# BSK4.net
KiCad netlist of a schematic drawn in EAGLE
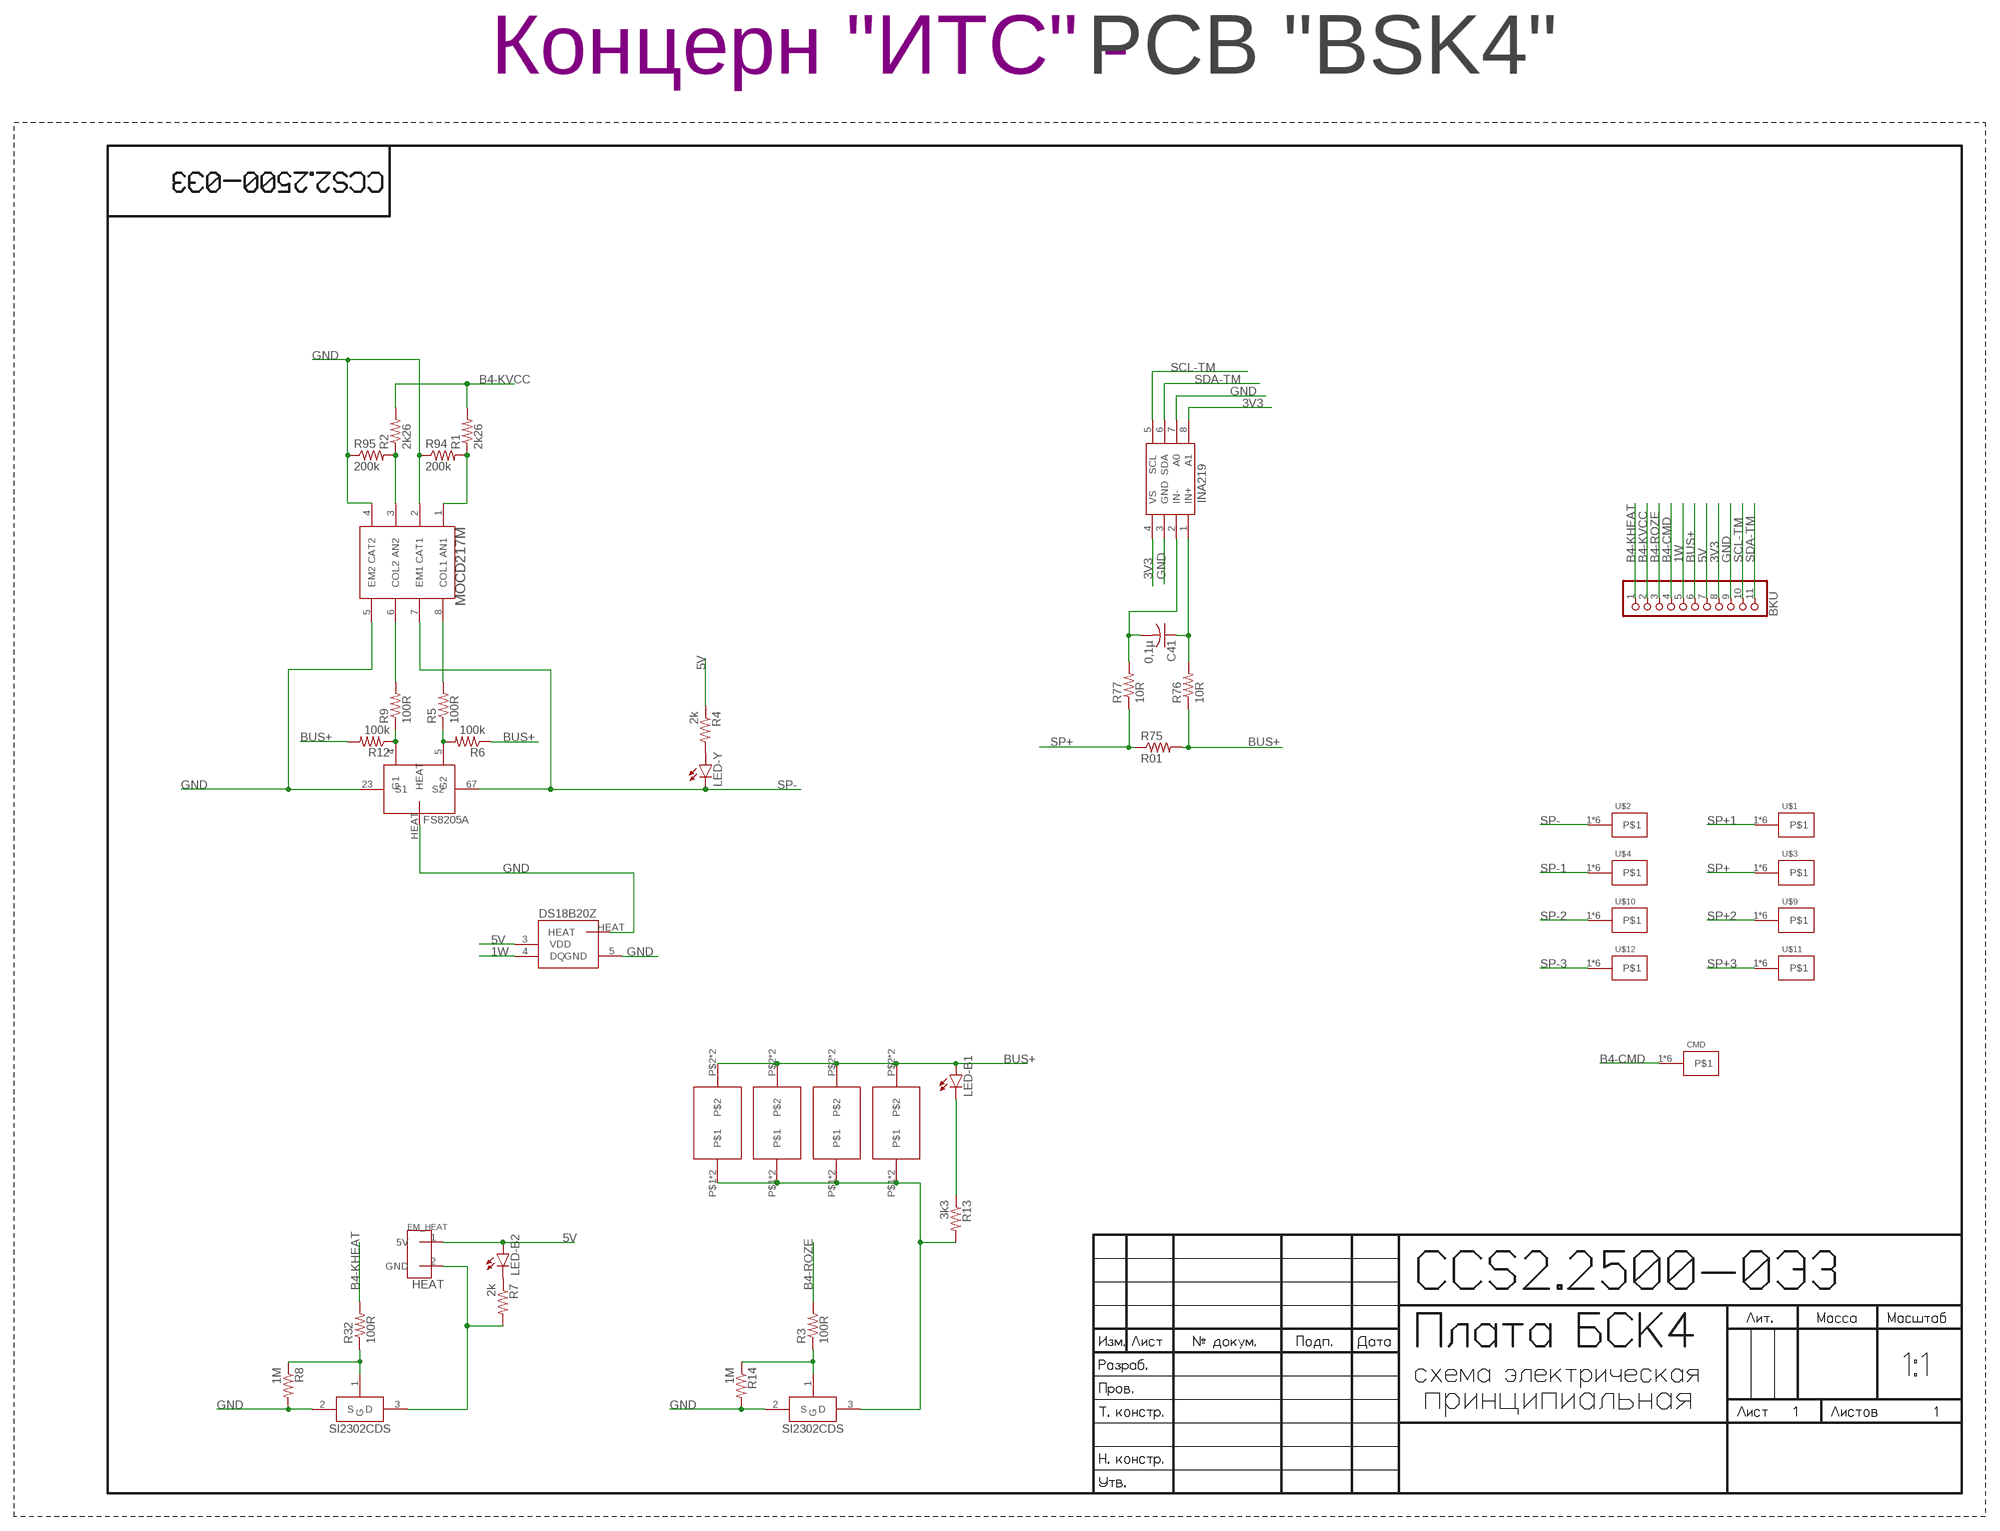
[diagram p0: schematic, sheet 1]

(export (version "E")
  (design (tool "Eeschema 10.0.6"))
  (components
    (comp (ref "BKU")
      (value "PINHD-1X11")
      (footprint "eagle-import:1X11")
      (libsource (lib "eagle-import") (part "PINHD-1X11"))
    )
    (comp (ref "C41")
      (value "0,1µ")
      (footprint "eagle-import:C0603")
      (libsource (lib "eagle-import") (part "C-USC0603"))
    )
    (comp (ref "CMD")
      (value "KCONNECTQUAD")
      (footprint "eagle-import:KCONNECT_QUAD")
      (libsource (lib "eagle-import") (part "KCONNECTQUAD"))
    )
    (comp (ref "DS18B20Z1")
      (value "DS18B20Z")
      (footprint "eagle-import:SOIC8+HEAT_S")
      (libsource (lib "eagle-import") (part "DS18B20Z"))
    )
    (comp (ref "INA")
      (value "INA219AID")
      (footprint "eagle-import:SOT23-8")
      (libsource (lib "eagle-import") (part "INA219AID"))
    )
    (comp (ref "LED-B1")
      (value "LEDCHIPLED_0603")
      (footprint "eagle-import:CHIPLED_0603")
      (libsource (lib "eagle-import") (part "LEDCHIPLED_0603"))
    )
    (comp (ref "LED-B2")
      (value "LEDCHIPLED_0603")
      (footprint "eagle-import:CHIPLED_0603")
      (libsource (lib "eagle-import") (part "LEDCHIPLED_0603"))
    )
    (comp (ref "LED-Y")
      (value "LAP4-BOTTOM")
      (footprint "eagle-import:P47F-BOTTOM")
      (libsource (lib "eagle-import") (part "P4-BOTTOMLA"))
    )
    (comp (ref "R1")
      (value "2k26")
      (footprint "eagle-import:R0603")
      (libsource (lib "eagle-import") (part "resistor_348_R-US_R0603"))
    )
    (comp (ref "R2")
      (value "2k26")
      (footprint "eagle-import:R0603")
      (libsource (lib "eagle-import") (part "resistor_348_R-US_R0603"))
    )
    (comp (ref "R3")
      (value "100R")
      (footprint "eagle-import:R0603")
      (libsource (lib "eagle-import") (part "resistor_R-US_R0603"))
    )
    (comp (ref "R4")
      (value "2k")
      (footprint "eagle-import:R0603")
      (libsource (lib "eagle-import") (part "resistor_348_R-US_R0603"))
    )
    (comp (ref "R5")
      (value "100R")
      (footprint "eagle-import:R0603")
      (libsource (lib "eagle-import") (part "resistor_348_R-US_R0603"))
    )
    (comp (ref "R6")
      (value "100k")
      (footprint "eagle-import:R0603")
      (libsource (lib "eagle-import") (part "resistor_348_R-US_R0603"))
    )
    (comp (ref "R7")
      (value "2k")
      (footprint "eagle-import:R0603")
      (libsource (lib "eagle-import") (part "resistor_348_R-US_R0603"))
    )
    (comp (ref "R8")
      (value "1M")
      (footprint "eagle-import:R0603")
      (libsource (lib "eagle-import") (part "resistor_348_R-US_R0603"))
    )
    (comp (ref "R9")
      (value "100R")
      (footprint "eagle-import:R0603")
      (libsource (lib "eagle-import") (part "resistor_348_R-US_R0603"))
    )
    (comp (ref "R12")
      (value "100k")
      (footprint "eagle-import:R0603")
      (libsource (lib "eagle-import") (part "resistor_348_R-US_R0603"))
    )
    (comp (ref "R13")
      (value "3k3")
      (footprint "eagle-import:R0603")
      (libsource (lib "eagle-import") (part "resistor_348_R-US_R0603"))
    )
    (comp (ref "R14")
      (value "1M")
      (footprint "eagle-import:R0603")
      (libsource (lib "eagle-import") (part "resistor_348_R-US_R0603"))
    )
    (comp (ref "R32")
      (value "100R")
      (footprint "eagle-import:R0603")
      (libsource (lib "eagle-import") (part "resistor_R-US_R0603"))
    )
    (comp (ref "R75")
      (value "R01")
      (footprint "eagle-import:R2512")
      (libsource (lib "eagle-import") (part "R-US_R2512"))
    )
    (comp (ref "R76")
      (value "10R")
      (footprint "eagle-import:R0603")
      (libsource (lib "eagle-import") (part "resistor_R-US_R0603"))
    )
    (comp (ref "R77")
      (value "10R")
      (footprint "eagle-import:R0603")
      (libsource (lib "eagle-import") (part "resistor_R-US_R0603"))
    )
    (comp (ref "R94")
      (value "200k")
      (footprint "eagle-import:R0603")
      (libsource (lib "eagle-import") (part "resistor_348_R-US_R0603"))
    )
    (comp (ref "R95")
      (value "200k")
      (footprint "eagle-import:R0603")
      (libsource (lib "eagle-import") (part "resistor_348_R-US_R0603"))
    )
    (comp (ref "U$1")
      (value "KCONNECT")
      (footprint "eagle-import:KCONNECT")
      (libsource (lib "eagle-import") (part "KCONNECT"))
    )
    (comp (ref "U$2")
      (value "KCONNECT")
      (footprint "eagle-import:KCONNECT")
      (libsource (lib "eagle-import") (part "KCONNECT"))
    )
    (comp (ref "U$3")
      (value "KCONNECT")
      (footprint "eagle-import:KCONNECT")
      (libsource (lib "eagle-import") (part "KCONNECT"))
    )
    (comp (ref "U$4")
      (value "KCONNECT")
      (footprint "eagle-import:KCONNECT")
      (libsource (lib "eagle-import") (part "KCONNECT"))
    )
    (comp (ref "U$5")
      (value "MOCD")
      (footprint "eagle-import:SOIC8")
      (libsource (lib "eagle-import") (part "MOCD217M"))
    )
    (comp (ref "U$6")
      (value "GRAFITGRAFIT4_2")
      (footprint "eagle-import:GRAFIT4_2")
      (libsource (lib "eagle-import") (part "GRAFITGRAFIT4_2"))
    )
    (comp (ref "U$7")
      (value "GRAFITGRAFIT4_2")
      (footprint "eagle-import:GRAFIT4_2")
      (libsource (lib "eagle-import") (part "GRAFITGRAFIT4_2"))
    )
    (comp (ref "U$8")
      (value "SI2302CDS")
      (footprint "eagle-import:SOT23-3")
      (libsource (lib "eagle-import") (part "SI2302CDS"))
    )
    (comp (ref "U$9")
      (value "KCONNECT")
      (footprint "eagle-import:KCONNECT")
      (libsource (lib "eagle-import") (part "KCONNECT"))
    )
    (comp (ref "U$10")
      (value "KCONNECT")
      (footprint "eagle-import:KCONNECT")
      (libsource (lib "eagle-import") (part "KCONNECT"))
    )
    (comp (ref "U$11")
      (value "KCONNECT")
      (footprint "eagle-import:KCONNECT")
      (libsource (lib "eagle-import") (part "KCONNECT"))
    )
    (comp (ref "U$12")
      (value "KCONNECT")
      (footprint "eagle-import:KCONNECT")
      (libsource (lib "eagle-import") (part "KCONNECT"))
    )
    (comp (ref "U$13")
      (value "SI2302CDS")
      (footprint "eagle-import:SOT23-3")
      (libsource (lib "eagle-import") (part "SI2302CDS"))
    )
    (comp (ref "U$14")
      (value "EM_HEAT")
      (footprint "eagle-import:EM_HEAT")
      (libsource (lib "eagle-import") (part "EM_HEAT"))
    )
    (comp (ref "U$15")
      (value "GRAFITGRAFIT4_2")
      (footprint "eagle-import:GRAFIT4_2")
      (libsource (lib "eagle-import") (part "GRAFITGRAFIT4_2"))
    )
    (comp (ref "U$16")
      (value "GRAFITGRAFIT4_2")
      (footprint "eagle-import:GRAFIT4_2")
      (libsource (lib "eagle-import") (part "GRAFITGRAFIT4_2"))
    )
    (comp (ref "U$17")
      (value "PCB \"BSK4\"")
      (footprint "eagle-import:ITS-LOGO")
      (libsource (lib "eagle-import") (part "ITS-LOGOPCB-{dblquote}{dblquote}"))
    )
    (comp (ref "U$26")
      (value "FS8205A+")
      (footprint "eagle-import:FS8205A+")
      (libsource (lib "eagle-import") (part "FS8205A+"))
    )
  )
  (nets
    (net (code "1") (name "/1W") (class "Default")
      (node (ref "BKU") (pin "5") (pinfunction "5_5") (pintype "passive"))
      (node (ref "DS18B20Z1") (pin "4") (pinfunction "DQ_4") (pintype "bidirectional"))
    )
    (net (code "2") (name "/3V3") (class "Default")
      (node (ref "BKU") (pin "8") (pinfunction "8_8") (pintype "passive"))
      (node (ref "INA") (pin "4") (pinfunction "VS_4") (pintype "bidirectional"))
      (node (ref "INA") (pin "8") (pinfunction "A1_8") (pintype "bidirectional"))
    )
    (net (code "3") (name "/5V") (class "Default")
      (node (ref "BKU") (pin "7") (pinfunction "7_7") (pintype "passive"))
      (node (ref "DS18B20Z1") (pin "3") (pinfunction "VDD_3") (pintype "bidirectional"))
      (node (ref "LED-B2") (pin "A") (pinfunction "A_A") (pintype "passive"))
      (node (ref "R4") (pin "1") (pinfunction "1_1") (pintype "passive"))
      (node (ref "U$14") (pin "1") (pinfunction "5V_1") (pintype "bidirectional"))
    )
    (net (code "4") (name "/B4-CMD") (class "Default")
      (node (ref "BKU") (pin "4") (pinfunction "4_4") (pintype "passive"))
      (node (ref "CMD") (pin "1") (pinfunction "P$1_1") (pintype "bidirectional"))
      (node (ref "CMD") (pin "2") (pinfunction "P$1_2") (pintype "bidirectional"))
      (node (ref "CMD") (pin "3") (pinfunction "P$1_3") (pintype "bidirectional"))
      (node (ref "CMD") (pin "4") (pinfunction "P$1_4") (pintype "bidirectional"))
      (node (ref "CMD") (pin "P$1") (pinfunction "P$1_P$1") (pintype "bidirectional"))
      (node (ref "CMD") (pin "P$2") (pinfunction "P$1_P$2") (pintype "bidirectional"))
    )
    (net (code "5") (name "/B4-KHEAT") (class "Default")
      (node (ref "BKU") (pin "1") (pinfunction "1_1") (pintype "passive"))
      (node (ref "R32") (pin "2") (pinfunction "2_2") (pintype "passive"))
    )
    (net (code "6") (name "/B4-KVCC") (class "Default")
      (node (ref "BKU") (pin "2") (pinfunction "2_2") (pintype "passive"))
      (node (ref "R1") (pin "2") (pinfunction "2_2") (pintype "passive"))
      (node (ref "R2") (pin "2") (pinfunction "2_2") (pintype "passive"))
    )
    (net (code "7") (name "/B4-ROZE") (class "Default")
      (node (ref "BKU") (pin "3") (pinfunction "3_3") (pintype "passive"))
      (node (ref "R3") (pin "2") (pinfunction "2_2") (pintype "passive"))
    )
    (net (code "8") (name "/BUS+") (class "Default")
      (node (ref "BKU") (pin "6") (pinfunction "6_6") (pintype "passive"))
      (node (ref "LED-B1") (pin "A") (pinfunction "A_A") (pintype "passive"))
      (node (ref "R12") (pin "2") (pinfunction "2_2") (pintype "passive"))
      (node (ref "R6") (pin "1") (pinfunction "1_1") (pintype "passive"))
      (node (ref "R75") (pin "2") (pinfunction "2_2") (pintype "passive"))
      (node (ref "R76") (pin "1") (pinfunction "1_1") (pintype "passive"))
      (node (ref "U$15") (pin "P$2") (pinfunction "P$2_P$2") (pintype "bidirectional"))
      (node (ref "U$15") (pin "P$5") (pinfunction "P$2_P$5") (pintype "bidirectional"))
      (node (ref "U$16") (pin "P$2") (pinfunction "P$2_P$2") (pintype "bidirectional"))
      (node (ref "U$16") (pin "P$5") (pinfunction "P$2_P$5") (pintype "bidirectional"))
      (node (ref "U$6") (pin "P$2") (pinfunction "P$2_P$2") (pintype "bidirectional"))
      (node (ref "U$6") (pin "P$5") (pinfunction "P$2_P$5") (pintype "bidirectional"))
      (node (ref "U$7") (pin "P$2") (pinfunction "P$2_P$2") (pintype "bidirectional"))
      (node (ref "U$7") (pin "P$5") (pinfunction "P$2_P$5") (pintype "bidirectional"))
    )
    (net (code "9") (name "/GND") (class "Default")
      (node (ref "BKU") (pin "9") (pinfunction "9_9") (pintype "passive"))
      (node (ref "DS18B20Z1") (pin "5") (pinfunction "GND_5") (pintype "bidirectional"))
      (node (ref "DS18B20Z1") (pin "HEAT") (pinfunction "HEAT_HEAT") (pintype "bidirectional"))
      (node (ref "INA") (pin "3") (pinfunction "GND_3") (pintype "bidirectional"))
      (node (ref "INA") (pin "7") (pinfunction "A0_7") (pintype "bidirectional"))
      (node (ref "R14") (pin "2") (pinfunction "2_2") (pintype "passive"))
      (node (ref "R8") (pin "2") (pinfunction "2_2") (pintype "passive"))
      (node (ref "R94") (pin "1") (pinfunction "1_1") (pintype "passive"))
      (node (ref "R95") (pin "1") (pinfunction "1_1") (pintype "passive"))
      (node (ref "U$13") (pin "2") (pinfunction "S_2") (pintype "bidirectional"))
      (node (ref "U$26") (pin "23") (pinfunction "S1_23") (pintype "bidirectional"))
      (node (ref "U$26") (pin "HEAT") (pinfunction "HEAT_HEAT") (pintype "bidirectional"))
      (node (ref "U$5") (pin "2") (pinfunction "CAT1_2") (pintype "bidirectional"))
      (node (ref "U$5") (pin "4") (pinfunction "CAT2_4") (pintype "bidirectional"))
      (node (ref "U$5") (pin "5") (pinfunction "EM2_5") (pintype "bidirectional"))
      (node (ref "U$8") (pin "2") (pinfunction "S_2") (pintype "bidirectional"))
    )
    (net (code "10") (name "/SCL-TM") (class "Default")
      (node (ref "BKU") (pin "10") (pinfunction "10_10") (pintype "passive"))
      (node (ref "INA") (pin "5") (pinfunction "SCL_5") (pintype "bidirectional"))
    )
    (net (code "11") (name "/SDA-TM") (class "Default")
      (node (ref "BKU") (pin "11") (pinfunction "11_11") (pintype "passive"))
      (node (ref "INA") (pin "6") (pinfunction "SDA_6") (pintype "bidirectional"))
    )
    (net (code "12") (name "/SP+") (class "Default")
      (node (ref "R75") (pin "1") (pinfunction "1_1") (pintype "passive"))
      (node (ref "R77") (pin "1") (pinfunction "1_1") (pintype "passive"))
      (node (ref "U$3") (pin "1") (pinfunction "P$1_1") (pintype "bidirectional"))
      (node (ref "U$3") (pin "2") (pinfunction "P$1_2") (pintype "bidirectional"))
      (node (ref "U$3") (pin "3") (pinfunction "P$1_3") (pintype "bidirectional"))
      (node (ref "U$3") (pin "4") (pinfunction "P$1_4") (pintype "bidirectional"))
      (node (ref "U$3") (pin "P$1") (pinfunction "P$1_P$1") (pintype "bidirectional"))
      (node (ref "U$3") (pin "P$2") (pinfunction "P$1_P$2") (pintype "bidirectional"))
    )
    (net (code "13") (name "/SP+1") (class "Default")
      (node (ref "U$1") (pin "1") (pinfunction "P$1_1") (pintype "bidirectional"))
      (node (ref "U$1") (pin "2") (pinfunction "P$1_2") (pintype "bidirectional"))
      (node (ref "U$1") (pin "3") (pinfunction "P$1_3") (pintype "bidirectional"))
      (node (ref "U$1") (pin "4") (pinfunction "P$1_4") (pintype "bidirectional"))
      (node (ref "U$1") (pin "P$1") (pinfunction "P$1_P$1") (pintype "bidirectional"))
      (node (ref "U$1") (pin "P$2") (pinfunction "P$1_P$2") (pintype "bidirectional"))
    )
    (net (code "14") (name "/SP+2") (class "Default")
      (node (ref "U$9") (pin "1") (pinfunction "P$1_1") (pintype "bidirectional"))
      (node (ref "U$9") (pin "2") (pinfunction "P$1_2") (pintype "bidirectional"))
      (node (ref "U$9") (pin "3") (pinfunction "P$1_3") (pintype "bidirectional"))
      (node (ref "U$9") (pin "4") (pinfunction "P$1_4") (pintype "bidirectional"))
      (node (ref "U$9") (pin "P$1") (pinfunction "P$1_P$1") (pintype "bidirectional"))
      (node (ref "U$9") (pin "P$2") (pinfunction "P$1_P$2") (pintype "bidirectional"))
    )
    (net (code "15") (name "/SP+3") (class "Default")
      (node (ref "U$11") (pin "1") (pinfunction "P$1_1") (pintype "bidirectional"))
      (node (ref "U$11") (pin "2") (pinfunction "P$1_2") (pintype "bidirectional"))
      (node (ref "U$11") (pin "3") (pinfunction "P$1_3") (pintype "bidirectional"))
      (node (ref "U$11") (pin "4") (pinfunction "P$1_4") (pintype "bidirectional"))
      (node (ref "U$11") (pin "P$1") (pinfunction "P$1_P$1") (pintype "bidirectional"))
      (node (ref "U$11") (pin "P$2") (pinfunction "P$1_P$2") (pintype "bidirectional"))
    )
    (net (code "16") (name "/SP-") (class "Default")
      (node (ref "LED-Y") (pin "C") (pinfunction "C_C") (pintype "passive"))
      (node (ref "U$2") (pin "1") (pinfunction "P$1_1") (pintype "bidirectional"))
      (node (ref "U$2") (pin "2") (pinfunction "P$1_2") (pintype "bidirectional"))
      (node (ref "U$2") (pin "3") (pinfunction "P$1_3") (pintype "bidirectional"))
      (node (ref "U$2") (pin "4") (pinfunction "P$1_4") (pintype "bidirectional"))
      (node (ref "U$2") (pin "P$1") (pinfunction "P$1_P$1") (pintype "bidirectional"))
      (node (ref "U$2") (pin "P$2") (pinfunction "P$1_P$2") (pintype "bidirectional"))
      (node (ref "U$26") (pin "67") (pinfunction "S2_67") (pintype "bidirectional"))
      (node (ref "U$5") (pin "7") (pinfunction "EM1_7") (pintype "bidirectional"))
    )
    (net (code "17") (name "/SP-1") (class "Default")
      (node (ref "U$4") (pin "1") (pinfunction "P$1_1") (pintype "bidirectional"))
      (node (ref "U$4") (pin "2") (pinfunction "P$1_2") (pintype "bidirectional"))
      (node (ref "U$4") (pin "3") (pinfunction "P$1_3") (pintype "bidirectional"))
      (node (ref "U$4") (pin "4") (pinfunction "P$1_4") (pintype "bidirectional"))
      (node (ref "U$4") (pin "P$1") (pinfunction "P$1_P$1") (pintype "bidirectional"))
      (node (ref "U$4") (pin "P$2") (pinfunction "P$1_P$2") (pintype "bidirectional"))
    )
    (net (code "18") (name "/SP-2") (class "Default")
      (node (ref "U$10") (pin "1") (pinfunction "P$1_1") (pintype "bidirectional"))
      (node (ref "U$10") (pin "2") (pinfunction "P$1_2") (pintype "bidirectional"))
      (node (ref "U$10") (pin "3") (pinfunction "P$1_3") (pintype "bidirectional"))
      (node (ref "U$10") (pin "4") (pinfunction "P$1_4") (pintype "bidirectional"))
      (node (ref "U$10") (pin "P$1") (pinfunction "P$1_P$1") (pintype "bidirectional"))
      (node (ref "U$10") (pin "P$2") (pinfunction "P$1_P$2") (pintype "bidirectional"))
    )
    (net (code "19") (name "/SP-3") (class "Default")
      (node (ref "U$12") (pin "1") (pinfunction "P$1_1") (pintype "bidirectional"))
      (node (ref "U$12") (pin "2") (pinfunction "P$1_2") (pintype "bidirectional"))
      (node (ref "U$12") (pin "3") (pinfunction "P$1_3") (pintype "bidirectional"))
      (node (ref "U$12") (pin "4") (pinfunction "P$1_4") (pintype "bidirectional"))
      (node (ref "U$12") (pin "P$1") (pinfunction "P$1_P$1") (pintype "bidirectional"))
      (node (ref "U$12") (pin "P$2") (pinfunction "P$1_P$2") (pintype "bidirectional"))
    )
    (net (code "20") (name "Net-(INA-IN+)") (class "Default")
      (node (ref "C41") (pin "1") (pinfunction "1_1") (pintype "passive"))
      (node (ref "INA") (pin "1") (pinfunction "IN+_1") (pintype "bidirectional"))
      (node (ref "R76") (pin "2") (pinfunction "2_2") (pintype "passive"))
    )
    (net (code "21") (name "Net-(INA-IN-)") (class "Default")
      (node (ref "C41") (pin "2") (pinfunction "2_2") (pintype "passive"))
      (node (ref "INA") (pin "2") (pinfunction "IN-_2") (pintype "bidirectional"))
      (node (ref "R77") (pin "2") (pinfunction "2_2") (pintype "passive"))
    )
    (net (code "22") (name "Net-(LED-B1-PadC)") (class "Default")
      (node (ref "LED-B1") (pin "C") (pinfunction "C_C") (pintype "passive"))
      (node (ref "R13") (pin "1") (pinfunction "1_1") (pintype "passive"))
    )
    (net (code "23") (name "Net-(LED-B2-PadC)") (class "Default")
      (node (ref "LED-B2") (pin "C") (pinfunction "C_C") (pintype "passive"))
      (node (ref "R7") (pin "1") (pinfunction "1_1") (pintype "passive"))
    )
    (net (code "24") (name "Net-(LED-Y-PadA)") (class "Default")
      (node (ref "LED-Y") (pin "A") (pinfunction "A_A") (pintype "passive"))
      (node (ref "R4") (pin "2") (pinfunction "2_2") (pintype "passive"))
    )
    (net (code "25") (name "Net-(U$5-AN1)") (class "Default")
      (node (ref "R1") (pin "1") (pinfunction "1_1") (pintype "passive"))
      (node (ref "R94") (pin "2") (pinfunction "2_2") (pintype "passive"))
      (node (ref "U$5") (pin "1") (pinfunction "AN1_1") (pintype "bidirectional"))
    )
    (net (code "26") (name "Net-(U$5-AN2)") (class "Default")
      (node (ref "R2") (pin "1") (pinfunction "1_1") (pintype "passive"))
      (node (ref "R95") (pin "2") (pinfunction "2_2") (pintype "passive"))
      (node (ref "U$5") (pin "3") (pinfunction "AN2_3") (pintype "bidirectional"))
    )
    (net (code "27") (name "Net-(U$5-COL1)") (class "Default")
      (node (ref "R5") (pin "2") (pinfunction "2_2") (pintype "passive"))
      (node (ref "U$5") (pin "8") (pinfunction "COL1_8") (pintype "bidirectional"))
    )
    (net (code "28") (name "Net-(U$5-COL2)") (class "Default")
      (node (ref "R9") (pin "2") (pinfunction "2_2") (pintype "passive"))
      (node (ref "U$5") (pin "6") (pinfunction "COL2_6") (pintype "bidirectional"))
    )
    (net (code "29") (name "Net-(U$8-G)") (class "Default")
      (node (ref "R32") (pin "1") (pinfunction "1_1") (pintype "passive"))
      (node (ref "R8") (pin "1") (pinfunction "1_1") (pintype "passive"))
      (node (ref "U$8") (pin "1") (pinfunction "G_1") (pintype "bidirectional"))
    )
    (net (code "30") (name "Net-(U$13-D)") (class "Default")
      (node (ref "R13") (pin "2") (pinfunction "2_2") (pintype "passive"))
      (node (ref "U$13") (pin "3") (pinfunction "D_3") (pintype "bidirectional"))
      (node (ref "U$15") (pin "P$1") (pinfunction "P$1_P$1") (pintype "bidirectional"))
      (node (ref "U$15") (pin "P$4") (pinfunction "P$1_P$4") (pintype "bidirectional"))
      (node (ref "U$16") (pin "P$1") (pinfunction "P$1_P$1") (pintype "bidirectional"))
      (node (ref "U$16") (pin "P$4") (pinfunction "P$1_P$4") (pintype "bidirectional"))
      (node (ref "U$6") (pin "P$1") (pinfunction "P$1_P$1") (pintype "bidirectional"))
      (node (ref "U$6") (pin "P$4") (pinfunction "P$1_P$4") (pintype "bidirectional"))
      (node (ref "U$7") (pin "P$1") (pinfunction "P$1_P$1") (pintype "bidirectional"))
      (node (ref "U$7") (pin "P$4") (pinfunction "P$1_P$4") (pintype "bidirectional"))
    )
    (net (code "31") (name "Net-(U$13-G)") (class "Default")
      (node (ref "R14") (pin "1") (pinfunction "1_1") (pintype "passive"))
      (node (ref "R3") (pin "1") (pinfunction "1_1") (pintype "passive"))
      (node (ref "U$13") (pin "1") (pinfunction "G_1") (pintype "bidirectional"))
    )
    (net (code "32") (name "Net-(U$14-GND)") (class "Default")
      (node (ref "R7") (pin "2") (pinfunction "2_2") (pintype "passive"))
      (node (ref "U$14") (pin "2") (pinfunction "GND_2") (pintype "bidirectional"))
      (node (ref "U$8") (pin "3") (pinfunction "D_3") (pintype "bidirectional"))
    )
    (net (code "33") (name "Net-(U$26-G1)") (class "Default")
      (node (ref "R12") (pin "1") (pinfunction "1_1") (pintype "passive"))
      (node (ref "R9") (pin "1") (pinfunction "1_1") (pintype "passive"))
      (node (ref "U$26") (pin "4") (pinfunction "G1_4") (pintype "bidirectional"))
    )
    (net (code "34") (name "Net-(U$26-G2)") (class "Default")
      (node (ref "R5") (pin "1") (pinfunction "1_1") (pintype "passive"))
      (node (ref "R6") (pin "2") (pinfunction "2_2") (pintype "passive"))
      (node (ref "U$26") (pin "5") (pinfunction "G2_5") (pintype "bidirectional"))
    )
  )
)
